# Stratologger_sl100_Board.net
KiCad netlist of a schematic drawn in EAGLE
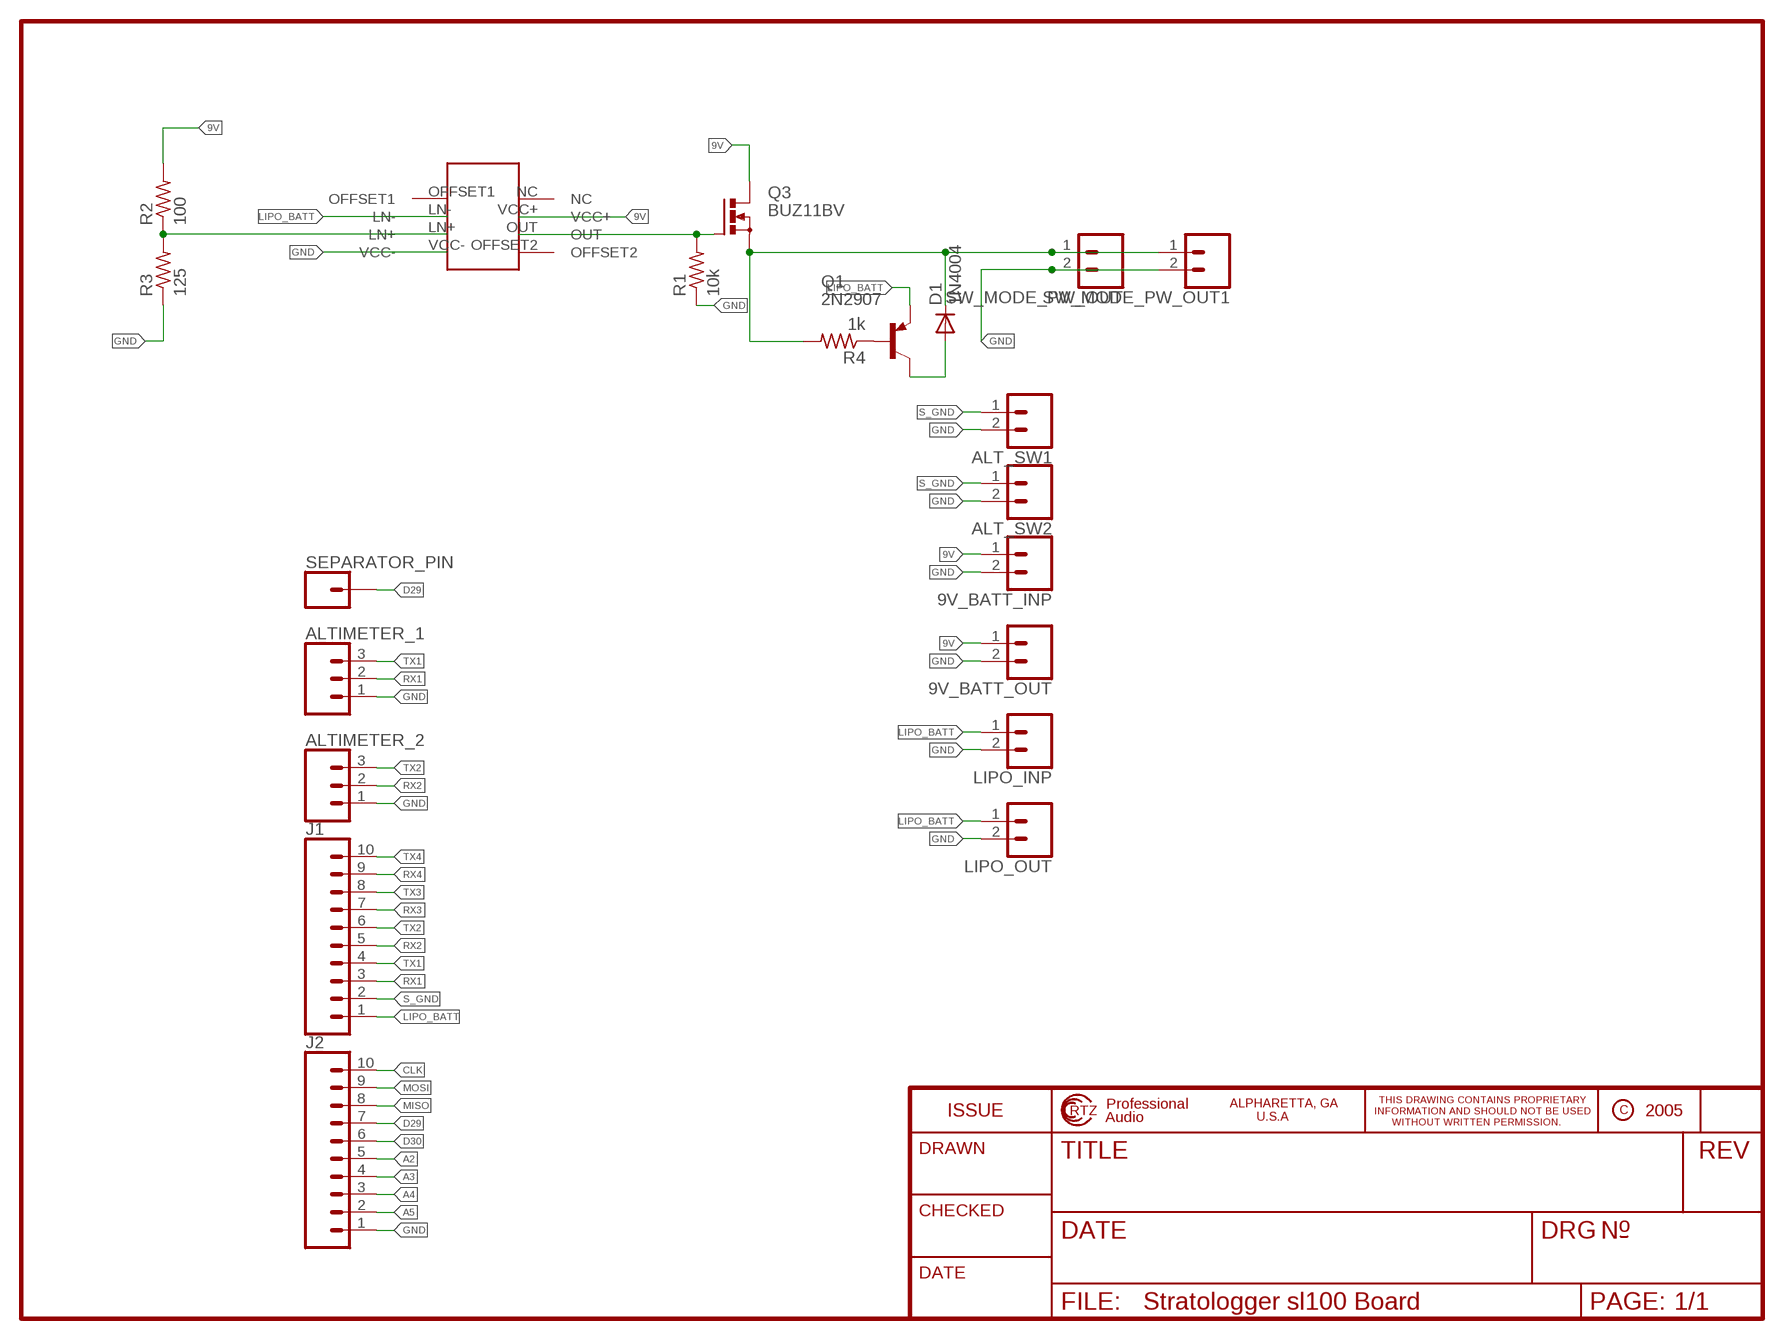
[diagram p0: schematic, sheet 1]

(export (version "E")
  (design (tool "Eeschema 10.0.6"))
  (components
    (comp (ref "9V_BATT_INP")
      (value "CONN_02")
      (footprint "eagle-import:1X02")
      (libsource (lib "eagle-import") (part "CONN_02"))
    )
    (comp (ref "9V_BATT_OUT")
      (value "CONN_02")
      (footprint "eagle-import:1X02")
      (libsource (lib "eagle-import") (part "CONN_02"))
    )
    (comp (ref "ALTIMETER_1")
      (value "CONN_03")
      (footprint "eagle-import:1X03")
      (libsource (lib "eagle-import") (part "CONN_03"))
    )
    (comp (ref "ALTIMETER_2")
      (value "CONN_03")
      (footprint "eagle-import:1X03")
      (libsource (lib "eagle-import") (part "CONN_03"))
    )
    (comp (ref "ALT_SW1")
      (value "CONN_02")
      (footprint "eagle-import:1X02")
      (libsource (lib "eagle-import") (part "CONN_02"))
    )
    (comp (ref "ALT_SW2")
      (value "CONN_02")
      (footprint "eagle-import:1X02")
      (libsource (lib "eagle-import") (part "CONN_02"))
    )
    (comp (ref "D1")
      (value "1N4004")
      (footprint "eagle-import:DO41-10")
      (libsource (lib "eagle-import") (part "1N4004"))
    )
    (comp (ref "J1")
      (value "CONN_10\"")
      (footprint "eagle-import:1X10")
      (libsource (lib "eagle-import") (part "CONN_10{dblquote}"))
    )
    (comp (ref "J2")
      (value "CONN_10\"")
      (footprint "eagle-import:1X10")
      (libsource (lib "eagle-import") (part "CONN_10{dblquote}"))
    )
    (comp (ref "LIPO_INP")
      (value "CONN_02")
      (footprint "eagle-import:1X02")
      (libsource (lib "eagle-import") (part "CONN_02"))
    )
    (comp (ref "LIPO_OUT")
      (value "CONN_02")
      (footprint "eagle-import:1X02")
      (libsource (lib "eagle-import") (part "CONN_02"))
    )
    (comp (ref "Q1")
      (value "2N2907")
      (footprint "eagle-import:TO92-EBC-OVAL")
      (libsource (lib "eagle-import") (part "2N2907"))
    )
    (comp (ref "Q3")
      (value "BUZ11BV")
      (footprint "eagle-import:TO220BV")
      (libsource (lib "eagle-import") (part "BUZ11BV"))
    )
    (comp (ref "R1")
      (value "10k")
      (footprint "eagle-import:0207_12")
      (libsource (lib "eagle-import") (part "R-US_0207/12"))
    )
    (comp (ref "R2")
      (value "100")
      (footprint "eagle-import:0207_12")
      (libsource (lib "eagle-import") (part "R-US_0207/12"))
    )
    (comp (ref "R3")
      (value "125")
      (footprint "eagle-import:0207_12")
      (libsource (lib "eagle-import") (part "R-US_0207/12"))
    )
    (comp (ref "R4")
      (value "1k")
      (footprint "eagle-import:0207_12")
      (libsource (lib "eagle-import") (part "R-US_0207/12"))
    )
    (comp (ref "SEPARATOR_PIN")
      (value "CONN_01")
      (footprint "eagle-import:1X01")
      (libsource (lib "eagle-import") (part "CONN_01"))
    )
    (comp (ref "SW_MODE_PW_OUT")
      (value "CONN_02")
      (footprint "eagle-import:1X02")
      (libsource (lib "eagle-import") (part "CONN_02"))
    )
    (comp (ref "SW_MODE_PW_OUT1")
      (value "CONN_02")
      (footprint "eagle-import:1X02")
      (libsource (lib "eagle-import") (part "CONN_02"))
    )
    (comp (ref "U$2")
      (value "STRATOLOGGER")
      (footprint "eagle-import:STRATOLOGGER")
      (libsource (lib "eagle-import") (part "STRATOLOGGER"))
    )
    (comp (ref "U$3")
      (value "LM471")
      (footprint "eagle-import:LM741")
      (libsource (lib "eagle-import") (part "LM471"))
    )
    (comp (ref "U$4")
      (value "STRATOLOGGER")
      (footprint "eagle-import:STRATOLOGGER")
      (libsource (lib "eagle-import") (part "STRATOLOGGER"))
    )
  )
  (nets
    (net (code "1") (name "9V") (class "Default")
      (node (ref "9V_BATT_INP") (pin "1") (pinfunction "1_1") (pintype "passive"))
      (node (ref "9V_BATT_OUT") (pin "1") (pinfunction "1_1") (pintype "passive"))
      (node (ref "Q3") (pin "D") (pinfunction "D_D") (pintype "passive"))
      (node (ref "R2") (pin "2") (pinfunction "2_2") (pintype "passive"))
      (node (ref "U$3") (pin "VCC+") (pinfunction "VCC+_VCC+") (pintype "bidirectional"))
    )
    (net (code "2") (name "A2") (class "Default")
      (node (ref "J2") (pin "5") (pinfunction "5_5") (pintype "passive"))
    )
    (net (code "3") (name "A3") (class "Default")
      (node (ref "J2") (pin "4") (pinfunction "4_4") (pintype "passive"))
    )
    (net (code "4") (name "A4") (class "Default")
      (node (ref "J2") (pin "3") (pinfunction "3_3") (pintype "passive"))
    )
    (net (code "5") (name "A5") (class "Default")
      (node (ref "J2") (pin "2") (pinfunction "2_2") (pintype "passive"))
    )
    (net (code "6") (name "CLK") (class "Default")
      (node (ref "J2") (pin "10") (pinfunction "10_10") (pintype "passive"))
    )
    (net (code "7") (name "D29") (class "Default")
      (node (ref "J2") (pin "7") (pinfunction "7_7") (pintype "passive"))
      (node (ref "SEPARATOR_PIN") (pin "1") (pinfunction "1_1") (pintype "passive"))
    )
    (net (code "8") (name "D30") (class "Default")
      (node (ref "J2") (pin "6") (pinfunction "6_6") (pintype "passive"))
    )
    (net (code "9") (name "GND") (class "Default")
      (node (ref "9V_BATT_INP") (pin "2") (pinfunction "2_2") (pintype "passive"))
      (node (ref "9V_BATT_OUT") (pin "2") (pinfunction "2_2") (pintype "passive"))
      (node (ref "ALTIMETER_1") (pin "1") (pinfunction "1_1") (pintype "passive"))
      (node (ref "ALTIMETER_2") (pin "1") (pinfunction "1_1") (pintype "passive"))
      (node (ref "ALT_SW1") (pin "2") (pinfunction "2_2") (pintype "passive"))
      (node (ref "ALT_SW2") (pin "2") (pinfunction "2_2") (pintype "passive"))
      (node (ref "J2") (pin "1") (pinfunction "1_1") (pintype "passive"))
      (node (ref "LIPO_INP") (pin "2") (pinfunction "2_2") (pintype "passive"))
      (node (ref "LIPO_OUT") (pin "2") (pinfunction "2_2") (pintype "passive"))
      (node (ref "R1") (pin "1") (pinfunction "1_1") (pintype "passive"))
      (node (ref "R3") (pin "1") (pinfunction "1_1") (pintype "passive"))
      (node (ref "SW_MODE_PW_OUT") (pin "2") (pinfunction "2_2") (pintype "passive"))
      (node (ref "SW_MODE_PW_OUT1") (pin "2") (pinfunction "2_2") (pintype "passive"))
      (node (ref "U$3") (pin "VCC-") (pinfunction "VCC-_VCC-") (pintype "bidirectional"))
    )
    (net (code "10") (name "LIPO_BATT") (class "Default")
      (node (ref "J1") (pin "1") (pinfunction "1_1") (pintype "passive"))
      (node (ref "LIPO_INP") (pin "1") (pinfunction "1_1") (pintype "passive"))
      (node (ref "LIPO_OUT") (pin "1") (pinfunction "1_1") (pintype "passive"))
      (node (ref "Q1") (pin "E") (pinfunction "E_E") (pintype "passive"))
      (node (ref "U$3") (pin "LN-") (pinfunction "LN-_LN-") (pintype "bidirectional"))
    )
    (net (code "11") (name "MISO") (class "Default")
      (node (ref "J2") (pin "8") (pinfunction "8_8") (pintype "passive"))
    )
    (net (code "12") (name "MOSI") (class "Default")
      (node (ref "J2") (pin "9") (pinfunction "9_9") (pintype "passive"))
    )
    (net (code "13") (name "Net-(D1-PadA)") (class "Default")
      (node (ref "D1") (pin "A") (pinfunction "A_A") (pintype "passive"))
      (node (ref "Q1") (pin "C") (pinfunction "C_C") (pintype "passive"))
    )
    (net (code "14") (name "Net-(D1-PadC)") (class "Default")
      (node (ref "D1") (pin "C") (pinfunction "C_C") (pintype "passive"))
      (node (ref "Q3") (pin "S") (pinfunction "S_S") (pintype "passive"))
      (node (ref "R4") (pin "2") (pinfunction "2_2") (pintype "passive"))
      (node (ref "SW_MODE_PW_OUT") (pin "1") (pinfunction "1_1") (pintype "passive"))
      (node (ref "SW_MODE_PW_OUT1") (pin "1") (pinfunction "1_1") (pintype "passive"))
    )
    (net (code "15") (name "Net-(Q1-PadB)") (class "Default")
      (node (ref "Q1") (pin "B") (pinfunction "B_B") (pintype "passive"))
      (node (ref "R4") (pin "1") (pinfunction "1_1") (pintype "passive"))
    )
    (net (code "16") (name "Net-(Q3-PadG)") (class "Default")
      (node (ref "Q3") (pin "G") (pinfunction "G_G") (pintype "passive"))
      (node (ref "R1") (pin "2") (pinfunction "2_2") (pintype "passive"))
      (node (ref "U$3") (pin "OUT") (pinfunction "OUT_OUT") (pintype "bidirectional"))
    )
    (net (code "17") (name "Net-(R2-Pad1)") (class "Default")
      (node (ref "R2") (pin "1") (pinfunction "1_1") (pintype "passive"))
      (node (ref "R3") (pin "2") (pinfunction "2_2") (pintype "passive"))
      (node (ref "U$3") (pin "LN+") (pinfunction "LN+_LN+") (pintype "bidirectional"))
    )
    (net (code "18") (name "RX1") (class "Default")
      (node (ref "ALTIMETER_1") (pin "2") (pinfunction "2_2") (pintype "passive"))
      (node (ref "J1") (pin "3") (pinfunction "3_3") (pintype "passive"))
    )
    (net (code "19") (name "RX2") (class "Default")
      (node (ref "ALTIMETER_2") (pin "2") (pinfunction "2_2") (pintype "passive"))
      (node (ref "J1") (pin "5") (pinfunction "5_5") (pintype "passive"))
    )
    (net (code "20") (name "RX3") (class "Default")
      (node (ref "J1") (pin "7") (pinfunction "7_7") (pintype "passive"))
    )
    (net (code "21") (name "RX4") (class "Default")
      (node (ref "J1") (pin "9") (pinfunction "9_9") (pintype "passive"))
    )
    (net (code "22") (name "S_GND") (class "Default")
      (node (ref "ALT_SW1") (pin "1") (pinfunction "1_1") (pintype "passive"))
      (node (ref "ALT_SW2") (pin "1") (pinfunction "1_1") (pintype "passive"))
      (node (ref "J1") (pin "2") (pinfunction "2_2") (pintype "passive"))
    )
    (net (code "23") (name "TX1") (class "Default")
      (node (ref "ALTIMETER_1") (pin "3") (pinfunction "3_3") (pintype "passive"))
      (node (ref "J1") (pin "4") (pinfunction "4_4") (pintype "passive"))
    )
    (net (code "24") (name "TX2") (class "Default")
      (node (ref "ALTIMETER_2") (pin "3") (pinfunction "3_3") (pintype "passive"))
      (node (ref "J1") (pin "6") (pinfunction "6_6") (pintype "passive"))
    )
    (net (code "25") (name "TX3") (class "Default")
      (node (ref "J1") (pin "8") (pinfunction "8_8") (pintype "passive"))
    )
    (net (code "26") (name "TX4") (class "Default")
      (node (ref "J1") (pin "10") (pinfunction "10_10") (pintype "passive"))
    )
    (net (code "27") (name "unconnected-(U$3-PadNC)") (class "Default")
      (node (ref "U$3") (pin "NC") (pinfunction "NC_NC") (pintype "bidirectional"))
    )
    (net (code "28") (name "unconnected-(U$3-PadOFFSET1)") (class "Default")
      (node (ref "U$3") (pin "OFFSET1") (pinfunction "OFFSET1_OFFSET1") (pintype "bidirectional"))
    )
    (net (code "29") (name "unconnected-(U$3-PadOFFSET2)") (class "Default")
      (node (ref "U$3") (pin "OFFSET2") (pinfunction "OFFSET2_OFFSET2") (pintype "bidirectional"))
    )
  )
)
